# CurrentSensingConverter.net
KiCad netlist of a schematic drawn in EAGLE
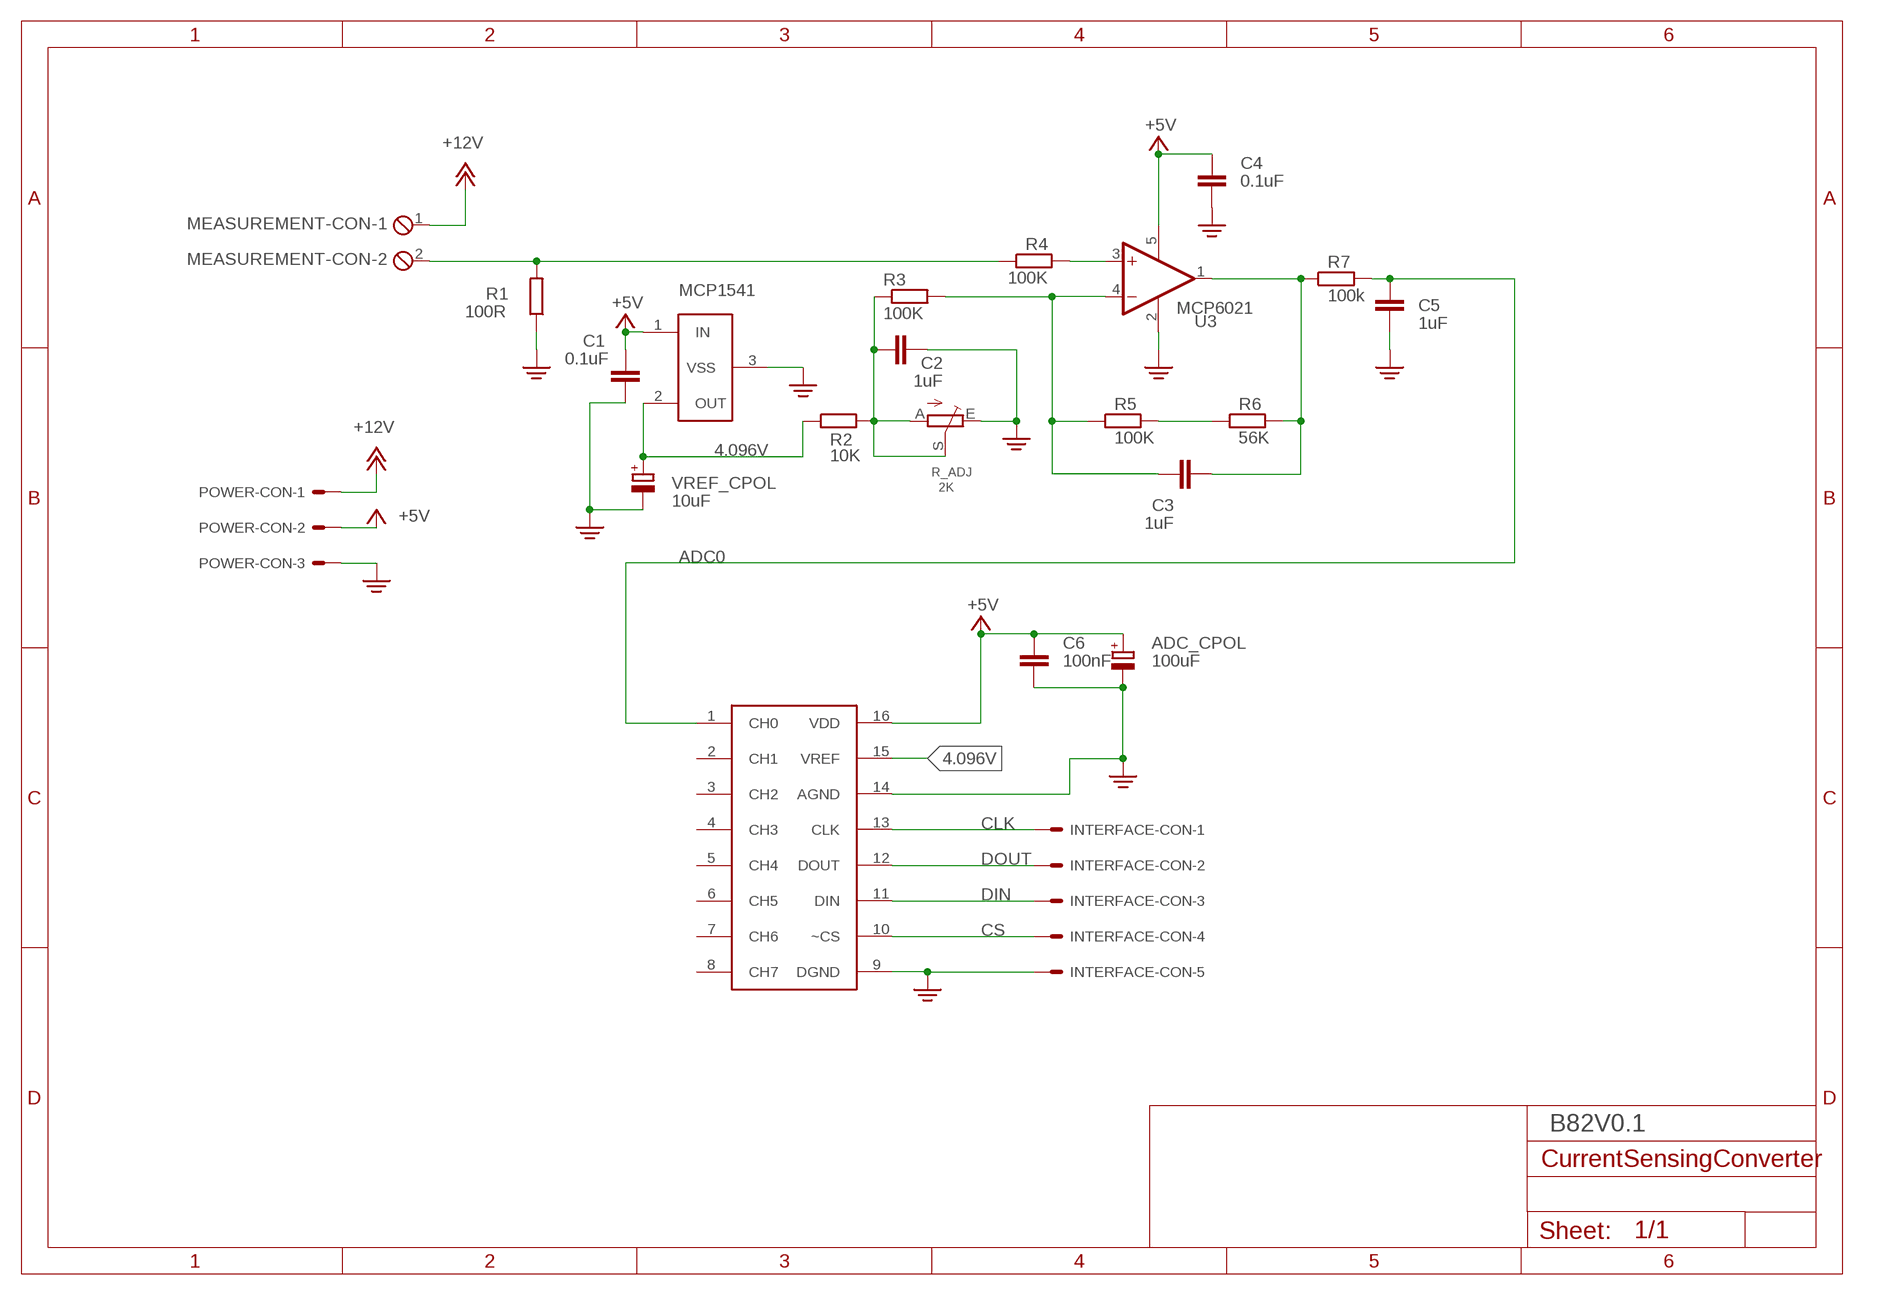
[diagram p0: schematic, sheet 1]

(export (version "E")
  (design (tool "Eeschema 10.0.6"))
  (components
    (comp (ref "ADC_CPOL")
      (value "100uF")
      (footprint "eagle-import:D_7343-31R")
      (libsource (lib "eagle-import") (part "CPOL-EUD/7343-31R"))
    )
    (comp (ref "C1")
      (value "0.1uF")
      (footprint "eagle-import:C1206")
      (libsource (lib "eagle-import") (part "C-EUC1206"))
    )
    (comp (ref "C2")
      (value "1uF")
      (footprint "eagle-import:C1206")
      (libsource (lib "eagle-import") (part "C-EUC1206"))
    )
    (comp (ref "C3")
      (value "1uF")
      (footprint "eagle-import:C1206")
      (libsource (lib "eagle-import") (part "C-EUC1206"))
    )
    (comp (ref "C4")
      (value "0.1uF")
      (footprint "eagle-import:C1206")
      (libsource (lib "eagle-import") (part "C-EUC1206"))
    )
    (comp (ref "C5")
      (value "1uF")
      (footprint "eagle-import:C1206")
      (libsource (lib "eagle-import") (part "C-EUC1206"))
    )
    (comp (ref "C6")
      (value "100nF")
      (footprint "eagle-import:C1206")
      (libsource (lib "eagle-import") (part "C-EUC1206"))
    )
    (comp (ref "INTERFACE-CON")
      (value "22-05-7058-05")
      (footprint "eagle-import:7395-05")
      (libsource (lib "eagle-import") (part "22-?-0505-7058"))
    )
    (comp (ref "MCP3208")
      (value "MCP3208-CI/SI")
      (footprint "eagle-import:SO16")
      (libsource (lib "eagle-import") (part "MCP3208-CI/SI"))
    )
    (comp (ref "MEASUREMENT-CON")
      (value "MPT2")
      (footprint "eagle-import:2POL254")
      (libsource (lib "eagle-import") (part "MPT2"))
    )
    (comp (ref "POWER-CON")
      (value "22-05-7038-03")
      (footprint "eagle-import:7395-03")
      (libsource (lib "eagle-import") (part "22-?-0305-7038"))
    )
    (comp (ref "R1")
      (value "100R")
      (footprint "eagle-import:R1206")
      (libsource (lib "eagle-import") (part "R-EU_R1206"))
    )
    (comp (ref "R2")
      (value "10K")
      (footprint "eagle-import:R1206")
      (libsource (lib "eagle-import") (part "R-EU_R1206"))
    )
    (comp (ref "R3")
      (value "100K")
      (footprint "eagle-import:R1206")
      (libsource (lib "eagle-import") (part "R-EU_R1206"))
    )
    (comp (ref "R4")
      (value "100K")
      (footprint "eagle-import:R1206")
      (libsource (lib "eagle-import") (part "R-EU_R1206"))
    )
    (comp (ref "R5")
      (value "100K")
      (footprint "eagle-import:R1206")
      (libsource (lib "eagle-import") (part "R-EU_R1206"))
    )
    (comp (ref "R6")
      (value "56K")
      (footprint "eagle-import:R1206")
      (libsource (lib "eagle-import") (part "R-EU_R1206"))
    )
    (comp (ref "R7")
      (value "100k")
      (footprint "eagle-import:R1206")
      (libsource (lib "eagle-import") (part "R-EU_R1206"))
    )
    (comp (ref "R_ADJ")
      (value "2K")
      (footprint "eagle-import:B25P")
      (libsource (lib "eagle-import") (part "TRIM_EU-B25P"))
    )
    (comp (ref "U1")
      (value "U1")
      (footprint "eagle-import:SOT23")
      (libsource (lib "eagle-import") (part "MCP1541T-I/TT"))
    )
    (comp (ref "U3")
      (value "MCP6021")
      (footprint "eagle-import:SOT23-5L")
      (libsource (lib "eagle-import") (part "MCP6021-SOT23"))
    )
    (comp (ref "VREF_CPOL")
      (value "10uF")
      (footprint "eagle-import:D_7343-31R")
      (libsource (lib "eagle-import") (part "CPOL-EUD/7343-31R"))
    )
  )
  (nets
    (net (code "1") (name "+5V") (class "Default")
      (node (ref "ADC_CPOL") (pin "+") (pinfunction "+_+") (pintype "passive"))
      (node (ref "C1") (pin "1") (pinfunction "1_1") (pintype "passive"))
      (node (ref "C4") (pin "1") (pinfunction "1_1") (pintype "passive"))
      (node (ref "C6") (pin "1") (pinfunction "1_1") (pintype "passive"))
      (node (ref "MCP3208") (pin "16") (pinfunction "VDD_16") (pintype "bidirectional"))
      (node (ref "POWER-CON") (pin "2") (pinfunction "S_2") (pintype "passive"))
      (node (ref "U1") (pin "1") (pinfunction "IN_1") (pintype "bidirectional"))
      (node (ref "U3") (pin "5") (pinfunction "V+_5") (pintype "power_in"))
    )
    (net (code "2") (name "+12V") (class "Default")
      (node (ref "MEASUREMENT-CON") (pin "1") (pinfunction "1_1") (pintype "passive"))
      (node (ref "POWER-CON") (pin "1") (pinfunction "S_1") (pintype "passive"))
    )
    (net (code "3") (name "/ADC0") (class "Default")
      (node (ref "C5") (pin "1") (pinfunction "1_1") (pintype "passive"))
      (node (ref "MCP3208") (pin "1") (pinfunction "CH0_1") (pintype "bidirectional"))
      (node (ref "R7") (pin "2") (pinfunction "2_2") (pintype "passive"))
    )
    (net (code "4") (name "/CLK") (class "Default")
      (node (ref "INTERFACE-CON") (pin "1") (pinfunction "S_1") (pintype "passive"))
      (node (ref "MCP3208") (pin "13") (pinfunction "CLK_13") (pintype "bidirectional"))
    )
    (net (code "5") (name "/CS") (class "Default")
      (node (ref "INTERFACE-CON") (pin "4") (pinfunction "S_4") (pintype "passive"))
      (node (ref "MCP3208") (pin "10") (pinfunction "~{CS}_10") (pintype "bidirectional"))
    )
    (net (code "6") (name "/DIN") (class "Default")
      (node (ref "INTERFACE-CON") (pin "3") (pinfunction "S_3") (pintype "passive"))
      (node (ref "MCP3208") (pin "11") (pinfunction "DIN_11") (pintype "bidirectional"))
    )
    (net (code "7") (name "/DOUT") (class "Default")
      (node (ref "INTERFACE-CON") (pin "2") (pinfunction "S_2") (pintype "passive"))
      (node (ref "MCP3208") (pin "12") (pinfunction "DOUT_12") (pintype "bidirectional"))
    )
    (net (code "8") (name "4.096V") (class "Default")
      (node (ref "MCP3208") (pin "15") (pinfunction "VREF_15") (pintype "bidirectional"))
      (node (ref "R2") (pin "1") (pinfunction "1_1") (pintype "passive"))
      (node (ref "U1") (pin "2") (pinfunction "OUT_2") (pintype "bidirectional"))
      (node (ref "VREF_CPOL") (pin "+") (pinfunction "+_+") (pintype "passive"))
    )
    (net (code "9") (name "Net-(C2-Pad1)") (class "Default")
      (node (ref "C2") (pin "1") (pinfunction "1_1") (pintype "passive"))
      (node (ref "R2") (pin "2") (pinfunction "2_2") (pintype "passive"))
      (node (ref "R3") (pin "1") (pinfunction "1_1") (pintype "passive"))
      (node (ref "R_ADJ") (pin "A") (pinfunction "A_A") (pintype "passive"))
      (node (ref "R_ADJ") (pin "S") (pinfunction "S_S") (pintype "passive"))
    )
    (net (code "10") (name "Net-(MEASUREMENT-CONB-1)") (class "Default")
      (node (ref "MEASUREMENT-CON") (pin "2") (pinfunction "1_2") (pintype "passive"))
      (node (ref "R1") (pin "2") (pinfunction "2_2") (pintype "passive"))
      (node (ref "R4") (pin "1") (pinfunction "1_1") (pintype "passive"))
    )
    (net (code "11") (name "Net-(R5-Pad2)") (class "Default")
      (node (ref "R5") (pin "2") (pinfunction "2_2") (pintype "passive"))
      (node (ref "R6") (pin "1") (pinfunction "1_1") (pintype "passive"))
    )
    (net (code "12") (name "Net-(U3-+IN)") (class "Default")
      (node (ref "R4") (pin "2") (pinfunction "2_2") (pintype "passive"))
      (node (ref "U3") (pin "3") (pinfunction "+IN_3") (pintype "input"))
    )
    (net (code "13") (name "Net-(U3--IN)") (class "Default")
      (node (ref "C3") (pin "1") (pinfunction "1_1") (pintype "passive"))
      (node (ref "R3") (pin "2") (pinfunction "2_2") (pintype "passive"))
      (node (ref "R5") (pin "1") (pinfunction "1_1") (pintype "passive"))
      (node (ref "U3") (pin "4") (pinfunction "-IN_4") (pintype "input"))
    )
    (net (code "14") (name "Net-(U3-OUT)") (class "Default")
      (node (ref "C3") (pin "2") (pinfunction "2_2") (pintype "passive"))
      (node (ref "R6") (pin "2") (pinfunction "2_2") (pintype "passive"))
      (node (ref "R7") (pin "1") (pinfunction "1_1") (pintype "passive"))
      (node (ref "U3") (pin "1") (pinfunction "OUT_1") (pintype "output"))
    )
    (net (code "15") (name "PE") (class "Default")
      (node (ref "ADC_CPOL") (pin "-") (pinfunction "-_-") (pintype "passive"))
      (node (ref "C1") (pin "2") (pinfunction "2_2") (pintype "passive"))
      (node (ref "C2") (pin "2") (pinfunction "2_2") (pintype "passive"))
      (node (ref "C4") (pin "2") (pinfunction "2_2") (pintype "passive"))
      (node (ref "C5") (pin "2") (pinfunction "2_2") (pintype "passive"))
      (node (ref "C6") (pin "2") (pinfunction "2_2") (pintype "passive"))
      (node (ref "INTERFACE-CON") (pin "5") (pinfunction "S_5") (pintype "passive"))
      (node (ref "MCP3208") (pin "14") (pinfunction "AGND_14") (pintype "bidirectional"))
      (node (ref "MCP3208") (pin "9") (pinfunction "DGND_9") (pintype "bidirectional"))
      (node (ref "POWER-CON") (pin "3") (pinfunction "S_3") (pintype "passive"))
      (node (ref "R1") (pin "1") (pinfunction "1_1") (pintype "passive"))
      (node (ref "R_ADJ") (pin "E") (pinfunction "E_E") (pintype "passive"))
      (node (ref "U1") (pin "3") (pinfunction "VSS_3") (pintype "bidirectional"))
      (node (ref "U3") (pin "2") (pinfunction "V-_2") (pintype "power_in"))
      (node (ref "VREF_CPOL") (pin "-") (pinfunction "-_-") (pintype "passive"))
    )
    (net (code "16") (name "unconnected-(MCP3208-CH1-Pad2)") (class "Default")
      (node (ref "MCP3208") (pin "2") (pinfunction "CH1_2") (pintype "bidirectional"))
    )
    (net (code "17") (name "unconnected-(MCP3208-CH2-Pad3)") (class "Default")
      (node (ref "MCP3208") (pin "3") (pinfunction "CH2_3") (pintype "bidirectional"))
    )
    (net (code "18") (name "unconnected-(MCP3208-CH3-Pad4)") (class "Default")
      (node (ref "MCP3208") (pin "4") (pinfunction "CH3_4") (pintype "bidirectional"))
    )
    (net (code "19") (name "unconnected-(MCP3208-CH4-Pad5)") (class "Default")
      (node (ref "MCP3208") (pin "5") (pinfunction "CH4_5") (pintype "bidirectional"))
    )
    (net (code "20") (name "unconnected-(MCP3208-CH5-Pad6)") (class "Default")
      (node (ref "MCP3208") (pin "6") (pinfunction "CH5_6") (pintype "bidirectional"))
    )
    (net (code "21") (name "unconnected-(MCP3208-CH6-Pad7)") (class "Default")
      (node (ref "MCP3208") (pin "7") (pinfunction "CH6_7") (pintype "bidirectional"))
    )
    (net (code "22") (name "unconnected-(MCP3208-CH7-Pad8)") (class "Default")
      (node (ref "MCP3208") (pin "8") (pinfunction "CH7_8") (pintype "bidirectional"))
    )
  )
)
